# ideal-diode.net
KiCad netlist of a schematic drawn in Altium Designer
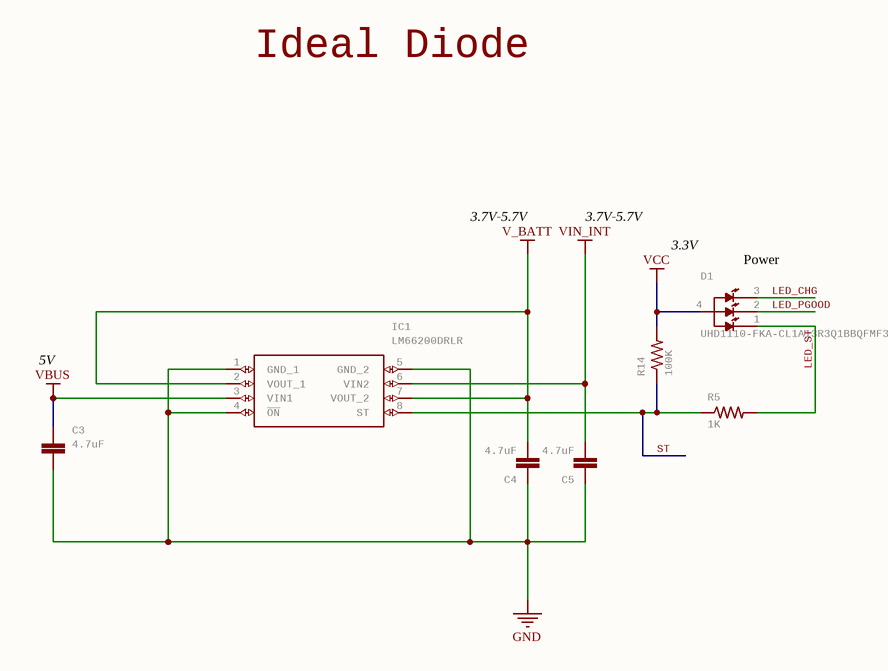
[diagram p0: ideal-diode.SchDoc]

(export (version "E")
  (design (tool "Eeschema 10.0.6"))
  (components
    (comp (ref "C3")
      (value "4.7uF")
      (footprint "0402-CAP")
      (description "CapacitorStandard 0603 ceramic capacitor, and 0.1\" leaded capacitor.")
      (fields (field (name "MPN") "JMK105BBJ475MV-F") (field (name "LIBRARYNAME") "sfe"))
      (libsource (lib "rt10") (part "CAP0402-CAP"))
    )
    (comp (ref "C4")
      (value "4.7uF")
      (footprint "0402-CAP")
      (description "CapacitorStandard 0603 ceramic capacitor, and 0.1\" leaded capacitor.")
      (fields (field (name "MPN") "JMK105BBJ475MV-F") (field (name "LIBRARYNAME") "sfe"))
      (libsource (lib "rt10") (part "CAP0402-CAP"))
    )
    (comp (ref "C5")
      (value "4.7uF")
      (footprint "0402-CAP")
      (description "CapacitorStandard 0603 ceramic capacitor, and 0.1\" leaded capacitor.")
      (fields (field (name "MPN") "JMK105BBJ475MV-F") (field (name "LIBRARYNAME") "sfe"))
      (libsource (lib "rt10") (part "CAP0402-CAP"))
    )
    (comp (ref "D1")
      (value "UHD1110-FKA-CL1A13R3Q1BBQFMF3")
      (footprint "LED_UHD1110-FKA-CL1A13R3Q1BBQFMF3")
      (description "LED RGB SMD, SIZE 1 X 1 mm Check availability")
      (fields (field (name "MF") "Cree Inc.") (field (name "MPN") "UHD1110-FKA-CL1A13r3q1BBQFMF3"))
      (libsource (lib "rt10") (part "UHD1110-FKA-CL1A13R3Q1BBQFMF3"))
    )
    (comp (ref "IC1")
      (value "LM66200DRLR")
      (footprint "SOTFL50P160X60-8N")
      (description "1.6-V to 5.5-V, 40-m, 2.5-A, low-IQ, dual ideal diode   Source:  Datasheet")
      (fields (field (name "MOUSER_PART_NUMBER") "595-LM66200DRLR"))
      (libsource (lib "rt10") (part "LM66200DRLR"))
    )
    (comp (ref "R5")
      (value "1K")
      (footprint "0402-RES")
      (description "ResistorBasic schematic elements and footprints for 0603, 1206, and PTH resistors.")
      (fields (field (name "MPN") "CRCW04021K00FKEDC") (field (name "LIBRARYNAME") "sfe"))
      (libsource (lib "rt10") (part "RESISTOR0402-RES"))
    )
    (comp (ref "R14")
      (value "100K")
      (footprint "0402-RES")
      (description "ResistorBasic schematic elements and footprints for 0603, 1206, and PTH resistors.")
      (fields (field (name "MPN") "AC0402FR-07100KL") (field (name "LIBRARYNAME") "sfe"))
      (libsource (lib "rt10") (part "RESISTOR0402-RES"))
    )
  )
  (nets
    (net (code "1") (name "/LED_CHG") (class "Default")
      (node (ref "D1") (pin "3") (pinfunction "RED_3") (pintype "passive"))
    )
    (net (code "2") (name "/LED_PGOOD") (class "Default")
      (node (ref "D1") (pin "2") (pinfunction "GREEN_2") (pintype "passive"))
    )
    (net (code "3") (name "/LED_ST") (class "Default")
      (node (ref "D1") (pin "1") (pinfunction "BLUE_1") (pintype "passive"))
      (node (ref "R5") (pin "2") (pinfunction "2_2") (pintype "passive"))
    )
    (net (code "4") (name "/ST") (class "Default")
      (node (ref "IC1") (pin "8") (pinfunction "ST_8") (pintype "bidirectional"))
      (node (ref "R14") (pin "1") (pinfunction "1_1") (pintype "passive"))
      (node (ref "R5") (pin "1") (pinfunction "1_1") (pintype "passive"))
    )
    (net (code "5") (name "GND") (class "Default")
      (node (ref "C3") (pin "1") (pinfunction "1_1") (pintype "passive"))
      (node (ref "C4") (pin "1") (pinfunction "1_1") (pintype "passive"))
      (node (ref "C5") (pin "1") (pinfunction "1_1") (pintype "passive"))
      (node (ref "IC1") (pin "1") (pinfunction "GND_1_1") (pintype "bidirectional"))
      (node (ref "IC1") (pin "4") (pinfunction "~{ON}_4") (pintype "bidirectional"))
      (node (ref "IC1") (pin "5") (pinfunction "GND_2_5") (pintype "bidirectional"))
    )
    (net (code "6") (name "VBUS") (class "Default")
      (node (ref "C3") (pin "2") (pinfunction "2_2") (pintype "passive"))
      (node (ref "IC1") (pin "3") (pinfunction "VIN1_3") (pintype "bidirectional"))
    )
    (net (code "7") (name "VCC") (class "Default")
      (node (ref "D1") (pin "4") (pinfunction "ANODE_4") (pintype "passive"))
      (node (ref "R14") (pin "2") (pinfunction "2_2") (pintype "passive"))
    )
    (net (code "8") (name "VIN_INT") (class "Default")
      (node (ref "C5") (pin "2") (pinfunction "2_2") (pintype "passive"))
      (node (ref "IC1") (pin "6") (pinfunction "VIN2_6") (pintype "bidirectional"))
    )
    (net (code "9") (name "V_BATT") (class "Default")
      (node (ref "C4") (pin "2") (pinfunction "2_2") (pintype "passive"))
      (node (ref "IC1") (pin "2") (pinfunction "VOUT_1_2") (pintype "bidirectional"))
      (node (ref "IC1") (pin "7") (pinfunction "VOUT_2_7") (pintype "bidirectional"))
    )
  )
)
